# TickBoard.net
KiCad netlist of a schematic drawn in EAGLE
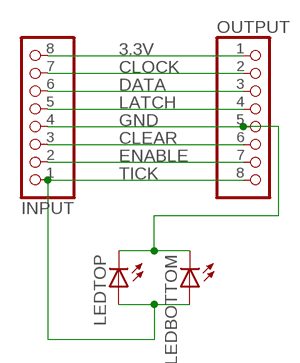
[diagram p0: schematic, sheet 1]

(export (version "E")
  (design (tool "Eeschema 10.0.6"))
  (components
    (comp (ref "INPUT")
      (value "PINHD-1X8/90")
      (footprint "eagle-import:1X08_90")
      (libsource (lib "eagle-import") (part "PINHD-1X8/90"))
    )
    (comp (ref "LEDBOTTOM")
      (value "LED5MM")
      (footprint "eagle-import:LED5MM")
      (libsource (lib "eagle-import") (part "LED5MM"))
    )
    (comp (ref "LEDTOP")
      (value "LED5MM")
      (footprint "eagle-import:LED5MM")
      (libsource (lib "eagle-import") (part "LED5MM"))
    )
    (comp (ref "OUTPUT")
      (value "PINHD-1X8/90")
      (footprint "eagle-import:1X08_90")
      (libsource (lib "eagle-import") (part "PINHD-1X8/90"))
    )
  )
  (nets
    (net (code "1") (name "/3.3V") (class "Default")
      (node (ref "INPUT") (pin "8") (pinfunction "8_8") (pintype "passive"))
      (node (ref "OUTPUT") (pin "1") (pinfunction "1_1") (pintype "passive"))
    )
    (net (code "2") (name "/CLEAR") (class "Default")
      (node (ref "INPUT") (pin "3") (pinfunction "3_3") (pintype "passive"))
      (node (ref "OUTPUT") (pin "6") (pinfunction "6_6") (pintype "passive"))
    )
    (net (code "3") (name "/CLOCK") (class "Default")
      (node (ref "INPUT") (pin "7") (pinfunction "7_7") (pintype "passive"))
      (node (ref "OUTPUT") (pin "2") (pinfunction "2_2") (pintype "passive"))
    )
    (net (code "4") (name "/DATA") (class "Default")
      (node (ref "INPUT") (pin "6") (pinfunction "6_6") (pintype "passive"))
      (node (ref "OUTPUT") (pin "3") (pinfunction "3_3") (pintype "passive"))
    )
    (net (code "5") (name "/ENABLE") (class "Default")
      (node (ref "INPUT") (pin "2") (pinfunction "2_2") (pintype "passive"))
      (node (ref "OUTPUT") (pin "7") (pinfunction "7_7") (pintype "passive"))
    )
    (net (code "6") (name "/GND") (class "Default")
      (node (ref "INPUT") (pin "4") (pinfunction "4_4") (pintype "passive"))
      (node (ref "LEDBOTTOM") (pin "K") (pinfunction "C_K") (pintype "passive"))
      (node (ref "LEDTOP") (pin "K") (pinfunction "C_K") (pintype "passive"))
      (node (ref "OUTPUT") (pin "5") (pinfunction "5_5") (pintype "passive"))
    )
    (net (code "7") (name "/LATCH") (class "Default")
      (node (ref "INPUT") (pin "5") (pinfunction "5_5") (pintype "passive"))
      (node (ref "OUTPUT") (pin "4") (pinfunction "4_4") (pintype "passive"))
    )
    (net (code "8") (name "/TICK") (class "Default")
      (node (ref "INPUT") (pin "1") (pinfunction "1_1") (pintype "passive"))
      (node (ref "LEDBOTTOM") (pin "A") (pinfunction "A_A") (pintype "passive"))
      (node (ref "LEDTOP") (pin "A") (pinfunction "A_A") (pintype "passive"))
      (node (ref "OUTPUT") (pin "8") (pinfunction "8_8") (pintype "passive"))
    )
  )
)
